# LFO.net
KiCad netlist of a schematic drawn in Altium Designer
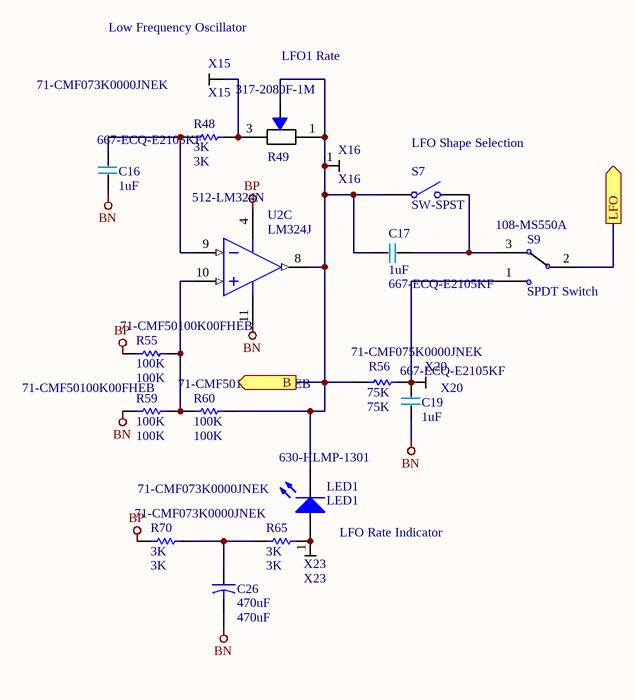
[diagram p0: LFO.SchDoc]

(export (version "E")
  (design (tool "Eeschema 10.0.6"))
  (components
    (comp (ref "C16")
      (value "1uF")
      (footprint "Cap Film 5")
      (fields
        (field (name "SUPPLIER PART NUMBER 1") "667-ECQ-E2105KF")
        (field (name "MANUFACTURER") "Panasonic")
        (field (name "MANUFACTURER PART NUMBER") "ECQ-E2105KF")
        (field (name "TOLERANCE") "10 %")
      )
      (libsource (lib "MyLibrary") (part "Cap Film 5"))
    )
    (comp (ref "C17")
      (value "1uF")
      (footprint "Cap Film 5")
      (fields
        (field (name "SUPPLIER PART NUMBER 1") "667-ECQ-E2105KF")
        (field (name "MANUFACTURER") "Panasonic")
        (field (name "MANUFACTURER PART NUMBER") "ECQ-E2105KF")
        (field (name "TOLERANCE") "10 %")
      )
      (libsource (lib "MyLibrary") (part "Cap Film 5"))
    )
    (comp (ref "C19")
      (value "1uF")
      (footprint "Cap Film 5")
      (fields
        (field (name "SUPPLIER PART NUMBER 1") "667-ECQ-E2105KF")
        (field (name "MANUFACTURER") "Panasonic")
        (field (name "MANUFACTURER PART NUMBER") "ECQ-E2105KF")
        (field (name "TOLERANCE") "10 %")
      )
      (libsource (lib "MyLibrary") (part "Cap Film 5"))
    )
    (comp (ref "C26")
      (value "470uF")
      (footprint "CAPR5-4X5")
      (description "Capacitor")
      (fields (field (name "ALTIUM_VALUE") "470uF") (field (name "PUBLISHER") "Altium Limited"))
      (libsource (lib "Miscellaneous Devices") (part "Cap2"))
    )
    (comp (ref "LED1")
      (value "LED1")
      (footprint "LED-0")
      (description "Typical INFRARED GaAs LED")
      (fields
        (field (name "SUPPLIER PART NUMBER 1") "630-HLMP-1301")
        (field (name "MANUFACTURER") "Broadcom / Avago")
        (field (name "MANUFACTURER PART NUMBER") "HLMP-1301")
        (field (name "PUBLISHER") "Altium Limited")
      )
      (libsource (lib "Miscellaneous Devices") (part "LED0"))
    )
    (comp (ref "R48")
      (value "3K")
      (footprint "AXIAL-0.3")
      (description "Resistor")
      (fields
        (field (name "ALTIUM_VALUE") "3K")
        (field (name "SUPPLIER PART NUMBER 1") "71-CMF073K0000JNEK")
        (field (name "MANUFACTURER") "Vishay / Dale")
        (field (name "MANUFACTURER PART NUMBER") "CMF073K0000JNEK")
        (field (name "PUBLISHER") "Altium Limited")
      )
      (libsource (lib "Miscellaneous Devices") (part "Res1"))
    )
    (comp (ref "R49")
      (value "1M")
      (footprint "Potentiometer")
      (description "My Own")
      (fields
        (field (name "SUPPLIER PART NUMBER 1") "317-2080F-1M")
        (field (name "MANUFACTURER") "Alpha (Taiwan)")
        (field (name "MANUFACTURER PART NUMBER") "RV09AF-40-20K-A16")
      )
      (libsource (lib "MyLibrary") (part "Potentiometer"))
    )
    (comp (ref "R55")
      (value "100K")
      (footprint "AXIAL-0.3")
      (description "Resistor")
      (fields
        (field (name "ALTIUM_VALUE") "100K")
        (field (name "MANUFACTURER") "Vishay / Dale")
        (field (name "MANUFACTURER PART NUMBER") "CMF55100K00FHEK")
        (field (name "SUPPLIER PART NUMBER 2") "71-CMF50100K00FHEB")
        (field (name "PUBLISHER") "Altium Limited")
      )
      (libsource (lib "Miscellaneous Devices") (part "Res1"))
    )
    (comp (ref "R56")
      (value "75K")
      (footprint "AXIAL-0.3")
      (description "Resistor")
      (fields
        (field (name "ALTIUM_VALUE") "75K")
        (field (name "SUPPLIER PART NUMBER 1") "71-CMF075K0000JNEK")
        (field (name "MANUFACTURER") "Yageo")
        (field (name "MANUFACTURER PART NUMBER") "FMP200FRF52-75K")
        (field (name "PUBLISHER") "Altium Limited")
      )
      (libsource (lib "Miscellaneous Devices") (part "Res1"))
    )
    (comp (ref "R59")
      (value "100K")
      (footprint "AXIAL-0.3")
      (description "Resistor")
      (fields
        (field (name "ALTIUM_VALUE") "100K")
        (field (name "MANUFACTURER") "Vishay / Dale")
        (field (name "MANUFACTURER PART NUMBER") "CMF55100K00FHEK")
        (field (name "SUPPLIER PART NUMBER 2") "71-CMF50100K00FHEB")
        (field (name "PUBLISHER") "Altium Limited")
      )
      (libsource (lib "Miscellaneous Devices") (part "Res1"))
    )
    (comp (ref "R60")
      (value "100K")
      (footprint "AXIAL-0.3")
      (description "Resistor")
      (fields
        (field (name "ALTIUM_VALUE") "100K")
        (field (name "MANUFACTURER") "Vishay / Dale")
        (field (name "MANUFACTURER PART NUMBER") "CMF55100K00FHEK")
        (field (name "SUPPLIER PART NUMBER 2") "71-CMF50100K00FHEB")
        (field (name "PUBLISHER") "Altium Limited")
      )
      (libsource (lib "Miscellaneous Devices") (part "Res1"))
    )
    (comp (ref "R65")
      (value "3K")
      (footprint "AXIAL-0.3")
      (description "Resistor")
      (fields
        (field (name "ALTIUM_VALUE") "3K")
        (field (name "SUPPLIER PART NUMBER 1") "71-CMF073K0000JNEK")
        (field (name "MANUFACTURER") "Vishay / Dale")
        (field (name "MANUFACTURER PART NUMBER") "CMF073K0000JNEK")
        (field (name "PUBLISHER") "Altium Limited")
      )
      (libsource (lib "Miscellaneous Devices") (part "Res1"))
    )
    (comp (ref "R70")
      (value "3K")
      (footprint "AXIAL-0.3")
      (description "Resistor")
      (fields
        (field (name "ALTIUM_VALUE") "3K")
        (field (name "SUPPLIER PART NUMBER 1") "71-CMF073K0000JNEK")
        (field (name "MANUFACTURER") "Vishay / Dale")
        (field (name "MANUFACTURER PART NUMBER") "CMF073K0000JNEK")
        (field (name "PUBLISHER") "Altium Limited")
      )
      (libsource (lib "Miscellaneous Devices") (part "Res1"))
    )
    (comp (ref "S7")
      (value "SW-SPST")
      (footprint "SPST-2")
      (description "Single-Pole, Single-Throw Switch")
      (fields (field (name "PUBLISHER") "Altium Limited"))
      (libsource (lib "Miscellaneous Devices") (part "SW-SPST"))
    )
    (comp (ref "S9")
      (value "SPDT Switch")
      (footprint "SPDT Switch")
      (fields
        (field (name "SUPPLIER PART NUMBER 1") "108-MS550A")
        (field (name "MANUFACTURER") "Mountain Switch")
        (field (name "MANUFACTURER PART NUMBER") "108-MS550A")
      )
      (libsource (lib "MyLibrary") (part "SPDT Switch"))
    )
    (comp (ref "U2")
      (value "LM324J")
      (footprint "J14A")
      (description "Low Power Quad Operational Amplifier, 14-pin CerDIP")
      (fields
        (field (name "MANUFACTURER") "National Semiconductor")
        (field (name "SUPPLIER PART NUMBER 1") "512-LM324N")
        (field (name "MANUFACTURER PART NUMBER") "LM324N")
      )
      (libsource (lib "National Semiconductor Amplifier") (part "LM324J"))
    )
    (comp (ref "X15") (value "X15") (footprint "Pad") (libsource (lib "MyLibrary") (part "Pad")))
    (comp (ref "X16") (value "X16") (footprint "Pad") (libsource (lib "") (part "Pad_1")))
    (comp (ref "X20") (value "X20") (footprint "Pad") (libsource (lib "MyLibrary") (part "Pad")))
    (comp (ref "X23") (value "X23") (footprint "Pad") (libsource (lib "") (part "Pad_1")))
  )
  (nets
    (net (code "1") (name "/B") (class "Default")
      (node (ref "C17") (pin "2") (pinfunction "2_2") (pintype "passive"))
      (node (ref "LED1") (pin "2") (pinfunction "K_2") (pintype "passive"))
      (node (ref "R49") (pin "1") (pinfunction "1_1") (pintype "passive"))
      (node (ref "R49") (pin "2") (pinfunction "2_2") (pintype "passive"))
      (node (ref "R56") (pin "1") (pinfunction "1_1") (pintype "passive"))
      (node (ref "R60") (pin "2") (pinfunction "2_2") (pintype "passive"))
      (node (ref "S7") (pin "1") (pinfunction "COMMON_1") (pintype "passive"))
      (node (ref "U2") (pin "8") (pinfunction "OUT3_8") (pintype "output"))
      (node (ref "X16") (pin "1") (pinfunction "1_1") (pintype "passive"))
    )
    (net (code "2") (name "/LFO") (class "Default")
      (node (ref "S9") (pin "2") (pinfunction "2_2") (pintype "passive"))
    )
    (net (code "3") (name "BN") (class "Default")
      (node (ref "C16") (pin "1") (pinfunction "1_1") (pintype "passive"))
      (node (ref "C19") (pin "1") (pinfunction "1_1") (pintype "passive"))
      (node (ref "C26") (pin "2") (pinfunction "2_2") (pintype "passive"))
      (node (ref "R59") (pin "1") (pinfunction "1_1") (pintype "passive"))
      (node (ref "U2") (pin "11") (pinfunction "GND_11") (pintype "power_in"))
    )
    (net (code "4") (name "BP") (class "Default")
      (node (ref "R55") (pin "1") (pinfunction "1_1") (pintype "passive"))
      (node (ref "R70") (pin "1") (pinfunction "1_1") (pintype "passive"))
      (node (ref "U2") (pin "4") (pinfunction "V+_4") (pintype "power_in"))
    )
    (net (code "5") (name "Net-(C19-Pad2)") (class "Default")
      (node (ref "C19") (pin "2") (pinfunction "2_2") (pintype "passive"))
      (node (ref "R56") (pin "2") (pinfunction "2_2") (pintype "passive"))
      (node (ref "S9") (pin "1") (pinfunction "1_1") (pintype "passive"))
      (node (ref "X20") (pin "1") (pinfunction "1_1") (pintype "passive"))
    )
    (net (code "6") (name "Net-(C26-Pad1)") (class "Default")
      (node (ref "C26") (pin "1") (pinfunction "1_1") (pintype "passive"))
      (node (ref "R65") (pin "1") (pinfunction "1_1") (pintype "passive"))
      (node (ref "R70") (pin "2") (pinfunction "2_2") (pintype "passive"))
    )
    (net (code "7") (name "Net-(LED1-A)") (class "Default")
      (node (ref "LED1") (pin "1") (pinfunction "A_1") (pintype "passive"))
      (node (ref "R65") (pin "2") (pinfunction "2_2") (pintype "passive"))
      (node (ref "X23") (pin "1") (pinfunction "1_1") (pintype "passive"))
    )
    (net (code "8") (name "Net-(R48-Pad2)") (class "Default")
      (node (ref "R48") (pin "2") (pinfunction "2_2") (pintype "passive"))
      (node (ref "R49") (pin "3") (pinfunction "3_3") (pintype "passive"))
      (node (ref "X15") (pin "1") (pinfunction "1_1") (pintype "passive"))
    )
    (net (code "9") (name "Net-(S7-NO)") (class "Default")
      (node (ref "C17") (pin "1") (pinfunction "1_1") (pintype "passive"))
      (node (ref "S7") (pin "2") (pinfunction "NO_2") (pintype "passive"))
      (node (ref "S9") (pin "3") (pinfunction "3_3") (pintype "passive"))
    )
    (net (code "10") (name "Net-(U2C-IN3+)") (class "Default")
      (node (ref "R55") (pin "2") (pinfunction "2_2") (pintype "passive"))
      (node (ref "R59") (pin "2") (pinfunction "2_2") (pintype "passive"))
      (node (ref "R60") (pin "1") (pinfunction "1_1") (pintype "passive"))
      (node (ref "U2") (pin "10") (pinfunction "IN3+_10") (pintype "input"))
    )
    (net (code "11") (name "Net-(U2C-IN3-)") (class "Default")
      (node (ref "C16") (pin "2") (pinfunction "2_2") (pintype "passive"))
      (node (ref "R48") (pin "1") (pinfunction "1_1") (pintype "passive"))
      (node (ref "U2") (pin "9") (pinfunction "IN3-_9") (pintype "input"))
    )
  )
)
